# ADCs.net
KiCad netlist of a schematic drawn in Altium Designer
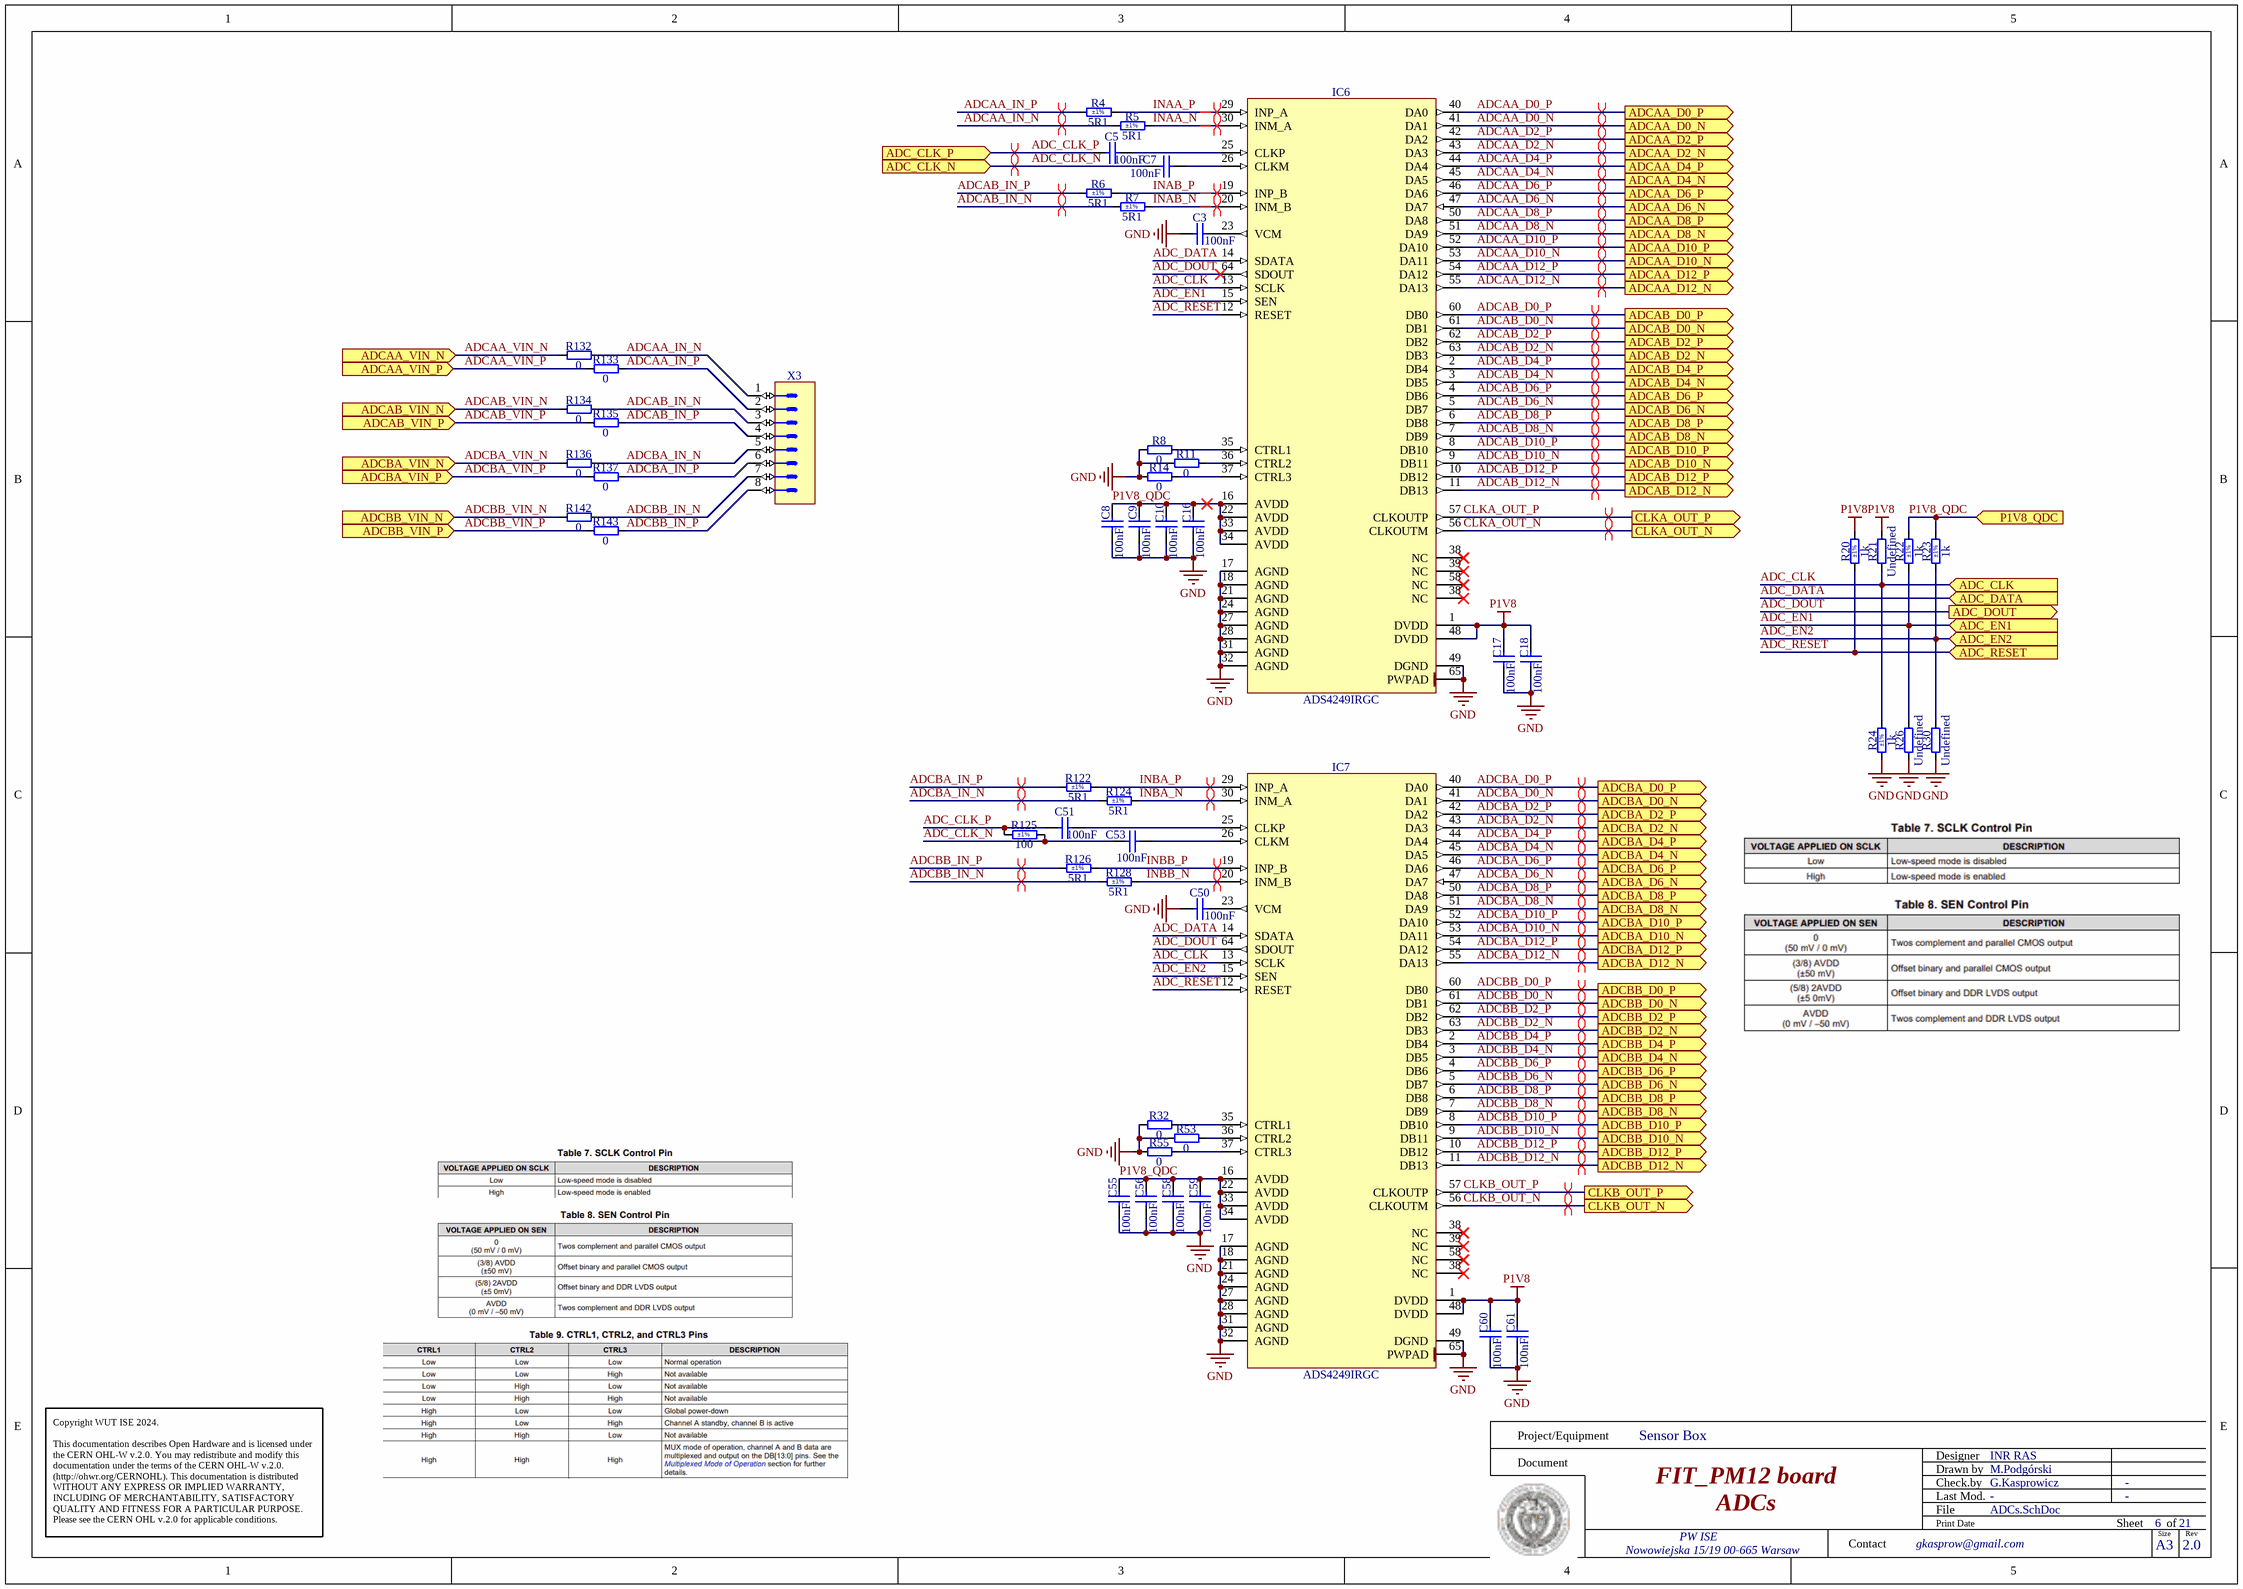
[diagram p0: ADCs.SchDoc]

(export (version "E")
  (design (tool "Eeschema 10.0.6"))
  (components
    (comp (ref "C3")
      (value "100nF")
      (footprint "CAPC1005X55N")
      (description "Non-polarised capacitor")
      (fields
        (field (name "PART NUMBER") "CC0402_100NF_16V_10%_X5R")
        (field (name "VOLTAGE") "16V")
        (field (name "AUTHOR") "CERN DEM JLC")
      )
      (libsource (lib "Capacitors") (part "Capacitor - non polarized"))
    )
    (comp (ref "C5")
      (value "100nF")
      (footprint "CAPC1005X55N")
      (description "Non-polarised capacitor")
      (fields
        (field (name "PART NUMBER") "CC0402_100NF_16V_10%_X5R")
        (field (name "VOLTAGE") "16V")
        (field (name "AUTHOR") "CERN DEM JLC")
      )
      (libsource (lib "Capacitors") (part "Capacitor - non polarized"))
    )
    (comp (ref "C7")
      (value "100nF")
      (footprint "CAPC1005X55N")
      (description "Non-polarised capacitor")
      (fields
        (field (name "PART NUMBER") "CC0402_100NF_16V_10%_X5R")
        (field (name "VOLTAGE") "16V")
        (field (name "AUTHOR") "CERN DEM JLC")
      )
      (libsource (lib "Capacitors") (part "Capacitor - non polarized"))
    )
    (comp (ref "C8")
      (value "100nF")
      (footprint "CAPC1005X55N")
      (description "Non-polarised capacitor")
      (fields
        (field (name "PART NUMBER") "CC0402_100NF_16V_10%_X5R")
        (field (name "VOLTAGE") "16V")
        (field (name "AUTHOR") "CERN DEM JLC")
      )
      (libsource (lib "Capacitors") (part "Capacitor - non polarized"))
    )
    (comp (ref "C9")
      (value "100nF")
      (footprint "CAPC1005X55N")
      (description "Non-polarised capacitor")
      (fields
        (field (name "PART NUMBER") "CC0402_100NF_16V_10%_X5R")
        (field (name "VOLTAGE") "16V")
        (field (name "AUTHOR") "CERN DEM JLC")
      )
      (libsource (lib "Capacitors") (part "Capacitor - non polarized"))
    )
    (comp (ref "C10")
      (value "100nF")
      (footprint "CAPC1005X55N")
      (description "Non-polarised capacitor")
      (fields
        (field (name "PART NUMBER") "CC0402_100NF_16V_10%_X5R")
        (field (name "VOLTAGE") "16V")
        (field (name "AUTHOR") "CERN DEM JLC")
      )
      (libsource (lib "Capacitors") (part "Capacitor - non polarized"))
    )
    (comp (ref "C16")
      (value "100nF")
      (footprint "CAPC1005X55N")
      (description "Non-polarised capacitor")
      (fields
        (field (name "PART NUMBER") "CC0402_100NF_16V_10%_X5R")
        (field (name "VOLTAGE") "16V")
        (field (name "AUTHOR") "CERN DEM JLC")
      )
      (libsource (lib "Capacitors") (part "Capacitor - non polarized"))
    )
    (comp (ref "C17")
      (value "100nF")
      (footprint "CAPC1005X55N")
      (description "Non-polarised capacitor")
      (fields
        (field (name "PART NUMBER") "CC0402_100NF_16V_10%_X5R")
        (field (name "VOLTAGE") "16V")
        (field (name "AUTHOR") "CERN DEM JLC")
      )
      (libsource (lib "Capacitors") (part "Capacitor - non polarized"))
    )
    (comp (ref "C18")
      (value "100nF")
      (footprint "CAPC1005X55N")
      (description "Non-polarised capacitor")
      (fields
        (field (name "PART NUMBER") "CC0402_100NF_16V_10%_X5R")
        (field (name "VOLTAGE") "16V")
        (field (name "AUTHOR") "CERN DEM JLC")
      )
      (libsource (lib "Capacitors") (part "Capacitor - non polarized"))
    )
    (comp (ref "C50")
      (value "100nF")
      (footprint "CAPC1005X55N")
      (description "Non-polarised capacitor")
      (fields
        (field (name "PART NUMBER") "CC0402_100NF_16V_10%_X5R")
        (field (name "VOLTAGE") "16V")
        (field (name "AUTHOR") "CERN DEM JLC")
      )
      (libsource (lib "Capacitors") (part "Capacitor - non polarized"))
    )
    (comp (ref "C51")
      (value "100nF")
      (footprint "CAPC1005X55N")
      (description "Non-polarised capacitor")
      (fields
        (field (name "PART NUMBER") "CC0402_100NF_16V_10%_X5R")
        (field (name "VOLTAGE") "16V")
        (field (name "AUTHOR") "CERN DEM JLC")
      )
      (libsource (lib "Capacitors") (part "Capacitor - non polarized"))
    )
    (comp (ref "C53")
      (value "100nF")
      (footprint "CAPC1005X55N")
      (description "Non-polarised capacitor")
      (fields
        (field (name "PART NUMBER") "CC0402_100NF_16V_10%_X5R")
        (field (name "VOLTAGE") "16V")
        (field (name "AUTHOR") "CERN DEM JLC")
      )
      (libsource (lib "Capacitors") (part "Capacitor - non polarized"))
    )
    (comp (ref "C55")
      (value "100nF")
      (footprint "CAPC1005X55N")
      (description "Non-polarised capacitor")
      (fields
        (field (name "PART NUMBER") "CC0402_100NF_16V_10%_X5R")
        (field (name "VOLTAGE") "16V")
        (field (name "AUTHOR") "CERN DEM JLC")
      )
      (libsource (lib "Capacitors") (part "Capacitor - non polarized"))
    )
    (comp (ref "C56")
      (value "100nF")
      (footprint "CAPC1005X55N")
      (description "Non-polarised capacitor")
      (fields
        (field (name "PART NUMBER") "CC0402_100NF_16V_10%_X5R")
        (field (name "VOLTAGE") "16V")
        (field (name "AUTHOR") "CERN DEM JLC")
      )
      (libsource (lib "Capacitors") (part "Capacitor - non polarized"))
    )
    (comp (ref "C58")
      (value "100nF")
      (footprint "CAPC1005X55N")
      (description "Non-polarised capacitor")
      (fields
        (field (name "PART NUMBER") "CC0402_100NF_16V_10%_X5R")
        (field (name "VOLTAGE") "16V")
        (field (name "AUTHOR") "CERN DEM JLC")
      )
      (libsource (lib "Capacitors") (part "Capacitor - non polarized"))
    )
    (comp (ref "C59")
      (value "100nF")
      (footprint "CAPC1005X55N")
      (description "Non-polarised capacitor")
      (fields
        (field (name "PART NUMBER") "CC0402_100NF_16V_10%_X5R")
        (field (name "VOLTAGE") "16V")
        (field (name "AUTHOR") "CERN DEM JLC")
      )
      (libsource (lib "Capacitors") (part "Capacitor - non polarized"))
    )
    (comp (ref "C60")
      (value "100nF")
      (footprint "CAPC1005X55N")
      (description "Non-polarised capacitor")
      (fields
        (field (name "PART NUMBER") "CC0402_100NF_16V_10%_X5R")
        (field (name "VOLTAGE") "16V")
        (field (name "AUTHOR") "CERN DEM JLC")
      )
      (libsource (lib "Capacitors") (part "Capacitor - non polarized"))
    )
    (comp (ref "C61")
      (value "100nF")
      (footprint "CAPC1005X55N")
      (description "Non-polarised capacitor")
      (fields
        (field (name "PART NUMBER") "CC0402_100NF_16V_10%_X5R")
        (field (name "VOLTAGE") "16V")
        (field (name "AUTHOR") "CERN DEM JLC")
      )
      (libsource (lib "Capacitors") (part "Capacitor - non polarized"))
    )
    (comp (ref "IC6")
      (value "ADS4249IRGC")
      (footprint "QFN50P900X900X100-65N-S750")
      (description "16-Bit, 200-MSPS Analog-to-Digital Converters")
      (fields (field (name "MANUFACTURER") "TEXAS INSTRUMENTS") (field (name "AUTHOR") "CERN DEM HF"))
      (libsource (lib "ICs And Semiconductors") (part "ADS4249IRGC"))
    )
    (comp (ref "IC7")
      (value "ADS4249IRGC")
      (footprint "QFN50P900X900X100-65N-S750")
      (description "16-Bit, 200-MSPS Analog-to-Digital Converters")
      (fields (field (name "MANUFACTURER") "TEXAS INSTRUMENTS") (field (name "AUTHOR") "CERN DEM HF"))
      (libsource (lib "ICs And Semiconductors") (part "ADS4249IRGC"))
    )
    (comp (ref "R4")
      (value "5R1")
      (footprint "RESC1005X40N")
      (description "Resistor - 1%")
      (fields
        (field (name "TOLERANCE") "±1%")
        (field (name "PART NUMBER") "R0402_5R1_1%_0.0625W_100PPM")
        (field (name "POWER") "0.0625W")
        (field (name "AUTHOR") "CERN DEM MR")
      )
      (libsource (lib "Resistors") (part "Resistor - 1%"))
    )
    (comp (ref "R5")
      (value "5R1")
      (footprint "RESC1005X40N")
      (description "Resistor - 1%")
      (fields
        (field (name "TOLERANCE") "±1%")
        (field (name "PART NUMBER") "R0402_5R1_1%_0.0625W_100PPM")
        (field (name "POWER") "0.0625W")
        (field (name "AUTHOR") "CERN DEM MR")
      )
      (libsource (lib "Resistors") (part "Resistor - 1%"))
    )
    (comp (ref "R6")
      (value "5R1")
      (footprint "RESC1005X40N")
      (description "Resistor - 1%")
      (fields
        (field (name "TOLERANCE") "±1%")
        (field (name "PART NUMBER") "R0402_5R1_1%_0.0625W_100PPM")
        (field (name "POWER") "0.0625W")
        (field (name "AUTHOR") "CERN DEM MR")
      )
      (libsource (lib "Resistors") (part "Resistor - 1%"))
    )
    (comp (ref "R7")
      (value "5R1")
      (footprint "RESC1005X40N")
      (description "Resistor - 1%")
      (fields
        (field (name "TOLERANCE") "±1%")
        (field (name "PART NUMBER") "R0402_5R1_1%_0.0625W_100PPM")
        (field (name "POWER") "0.0625W")
        (field (name "AUTHOR") "CERN DEM MR")
      )
      (libsource (lib "Resistors") (part "Resistor - 1%"))
    )
    (comp (ref "R8")
      (value "0")
      (footprint "RESC1005X40N")
      (description "Resistor")
      (fields
        (field (name "PART NUMBER") "R0402_0R_JUMPER")
        (field (name "MANUFACTURER") "GENERIC")
        (field (name "AUTHOR") "CERN DEM JLC")
      )
      (libsource (lib "Resistors") (part "Resistor"))
    )
    (comp (ref "R11")
      (value "0")
      (footprint "RESC1005X40N")
      (description "Resistor")
      (fields
        (field (name "PART NUMBER") "R0402_0R_JUMPER")
        (field (name "MANUFACTURER") "GENERIC")
        (field (name "AUTHOR") "CERN DEM JLC")
      )
      (libsource (lib "Resistors") (part "Resistor"))
    )
    (comp (ref "R14")
      (value "0")
      (footprint "RESC1005X40N")
      (description "Resistor")
      (fields
        (field (name "PART NUMBER") "R0402_0R_JUMPER")
        (field (name "MANUFACTURER") "GENERIC")
        (field (name "AUTHOR") "CERN DEM JLC")
      )
      (libsource (lib "Resistors") (part "Resistor"))
    )
    (comp (ref "R20")
      (value "1k")
      (footprint "RESC1005X40N")
      (description "Resistor - 1%")
      (fields
        (field (name "TOLERANCE") "±1%")
        (field (name "PART NUMBER") "R0402_1K_1%_0.0625W_100PPM")
        (field (name "POWER") "0.0625W")
        (field (name "AUTHOR") "CERN DEM JLC")
      )
      (libsource (lib "Resistors") (part "Resistor - 1%"))
    )
    (comp (ref "R21")
      (value "Undefined")
      (footprint "RESC1005X40N")
      (description "Resistor")
      (fields (field (name "PART NUMBER") "R0402_NO-VALUE") (field (name "AUTHOR") "CERN DEM JLC"))
      (libsource (lib "Resistors") (part "Resistor"))
    )
    (comp (ref "R22")
      (value "1k")
      (footprint "RESC1005X40N")
      (description "Resistor - 1%")
      (fields
        (field (name "TOLERANCE") "±1%")
        (field (name "PART NUMBER") "R0402_1K_1%_0.0625W_100PPM")
        (field (name "POWER") "0.0625W")
        (field (name "AUTHOR") "CERN DEM JLC")
      )
      (libsource (lib "Resistors") (part "Resistor - 1%"))
    )
    (comp (ref "R23")
      (value "1k")
      (footprint "RESC1005X40N")
      (description "Resistor - 1%")
      (fields
        (field (name "TOLERANCE") "±1%")
        (field (name "PART NUMBER") "R0402_1K_1%_0.0625W_100PPM")
        (field (name "POWER") "0.0625W")
        (field (name "AUTHOR") "CERN DEM JLC")
      )
      (libsource (lib "Resistors") (part "Resistor - 1%"))
    )
    (comp (ref "R24")
      (value "1k")
      (footprint "RESC1005X40N")
      (description "Resistor - 1%")
      (fields
        (field (name "TOLERANCE") "±1%")
        (field (name "PART NUMBER") "R0402_1K_1%_0.0625W_100PPM")
        (field (name "POWER") "0.0625W")
        (field (name "AUTHOR") "CERN DEM JLC")
      )
      (libsource (lib "Resistors") (part "Resistor - 1%"))
    )
    (comp (ref "R26")
      (value "Undefined")
      (footprint "RESC1005X40N")
      (description "Resistor")
      (fields (field (name "PART NUMBER") "R0402_NO-VALUE") (field (name "AUTHOR") "CERN DEM JLC"))
      (libsource (lib "Resistors") (part "Resistor"))
    )
    (comp (ref "R30")
      (value "Undefined")
      (footprint "RESC1005X40N")
      (description "Resistor")
      (fields (field (name "PART NUMBER") "R0402_NO-VALUE") (field (name "AUTHOR") "CERN DEM JLC"))
      (libsource (lib "Resistors") (part "Resistor"))
    )
    (comp (ref "R32")
      (value "0")
      (footprint "RESC1005X40N")
      (description "Resistor")
      (fields
        (field (name "PART NUMBER") "R0402_0R_JUMPER")
        (field (name "MANUFACTURER") "GENERIC")
        (field (name "AUTHOR") "CERN DEM JLC")
      )
      (libsource (lib "Resistors") (part "Resistor"))
    )
    (comp (ref "R53")
      (value "0")
      (footprint "RESC1005X40N")
      (description "Resistor")
      (fields
        (field (name "PART NUMBER") "R0402_0R_JUMPER")
        (field (name "MANUFACTURER") "GENERIC")
        (field (name "AUTHOR") "CERN DEM JLC")
      )
      (libsource (lib "Resistors") (part "Resistor"))
    )
    (comp (ref "R55")
      (value "0")
      (footprint "RESC1005X40N")
      (description "Resistor")
      (fields
        (field (name "PART NUMBER") "R0402_0R_JUMPER")
        (field (name "MANUFACTURER") "GENERIC")
        (field (name "AUTHOR") "CERN DEM JLC")
      )
      (libsource (lib "Resistors") (part "Resistor"))
    )
    (comp (ref "R122")
      (value "5R1")
      (footprint "RESC1005X40N")
      (description "Resistor - 1%")
      (fields
        (field (name "TOLERANCE") "±1%")
        (field (name "PART NUMBER") "R0402_5R1_1%_0.0625W_100PPM")
        (field (name "POWER") "0.0625W")
        (field (name "AUTHOR") "CERN DEM MR")
      )
      (libsource (lib "Resistors") (part "Resistor - 1%"))
    )
    (comp (ref "R124")
      (value "5R1")
      (footprint "RESC1005X40N")
      (description "Resistor - 1%")
      (fields
        (field (name "TOLERANCE") "±1%")
        (field (name "PART NUMBER") "R0402_5R1_1%_0.0625W_100PPM")
        (field (name "POWER") "0.0625W")
        (field (name "AUTHOR") "CERN DEM MR")
      )
      (libsource (lib "Resistors") (part "Resistor - 1%"))
    )
    (comp (ref "R125")
      (value "100")
      (footprint "RESC1608X55N")
      (description "Resistor - 1%")
      (fields
        (field (name "TOLERANCE") "±1%")
        (field (name "PART NUMBER") "R0603_100R_1%_0.1W_100PPM")
        (field (name "POWER") "0.1W")
        (field (name "AUTHOR") "CERN DEM JLC")
      )
      (libsource (lib "Resistors") (part "Resistor - 1%"))
    )
    (comp (ref "R126")
      (value "5R1")
      (footprint "RESC1005X40N")
      (description "Resistor - 1%")
      (fields
        (field (name "TOLERANCE") "±1%")
        (field (name "PART NUMBER") "R0402_5R1_1%_0.0625W_100PPM")
        (field (name "POWER") "0.0625W")
        (field (name "AUTHOR") "CERN DEM MR")
      )
      (libsource (lib "Resistors") (part "Resistor - 1%"))
    )
    (comp (ref "R128")
      (value "5R1")
      (footprint "RESC1005X40N")
      (description "Resistor - 1%")
      (fields
        (field (name "TOLERANCE") "±1%")
        (field (name "PART NUMBER") "R0402_5R1_1%_0.0625W_100PPM")
        (field (name "POWER") "0.0625W")
        (field (name "AUTHOR") "CERN DEM MR")
      )
      (libsource (lib "Resistors") (part "Resistor - 1%"))
    )
    (comp (ref "R132")
      (value "0")
      (footprint "RESC1005X40N")
      (description "Resistor")
      (fields
        (field (name "PART NUMBER") "R0402_0R_JUMPER")
        (field (name "MANUFACTURER") "GENERIC")
        (field (name "AUTHOR") "CERN DEM JLC")
      )
      (libsource (lib "Resistors") (part "Resistor"))
    )
    (comp (ref "R133")
      (value "0")
      (footprint "RESC1005X40N")
      (description "Resistor")
      (fields
        (field (name "PART NUMBER") "R0402_0R_JUMPER")
        (field (name "MANUFACTURER") "GENERIC")
        (field (name "AUTHOR") "CERN DEM JLC")
      )
      (libsource (lib "Resistors") (part "Resistor"))
    )
    (comp (ref "R134")
      (value "0")
      (footprint "RESC1005X40N")
      (description "Resistor")
      (fields
        (field (name "PART NUMBER") "R0402_0R_JUMPER")
        (field (name "MANUFACTURER") "GENERIC")
        (field (name "AUTHOR") "CERN DEM JLC")
      )
      (libsource (lib "Resistors") (part "Resistor"))
    )
    (comp (ref "R135")
      (value "0")
      (footprint "RESC1005X40N")
      (description "Resistor")
      (fields
        (field (name "PART NUMBER") "R0402_0R_JUMPER")
        (field (name "MANUFACTURER") "GENERIC")
        (field (name "AUTHOR") "CERN DEM JLC")
      )
      (libsource (lib "Resistors") (part "Resistor"))
    )
    (comp (ref "R136")
      (value "0")
      (footprint "RESC1005X40N")
      (description "Resistor")
      (fields
        (field (name "PART NUMBER") "R0402_0R_JUMPER")
        (field (name "MANUFACTURER") "GENERIC")
        (field (name "AUTHOR") "CERN DEM JLC")
      )
      (libsource (lib "Resistors") (part "Resistor"))
    )
    (comp (ref "R137")
      (value "0")
      (footprint "RESC1005X40N")
      (description "Resistor")
      (fields
        (field (name "PART NUMBER") "R0402_0R_JUMPER")
        (field (name "MANUFACTURER") "GENERIC")
        (field (name "AUTHOR") "CERN DEM JLC")
      )
      (libsource (lib "Resistors") (part "Resistor"))
    )
    (comp (ref "R142")
      (value "0")
      (footprint "RESC1005X40N")
      (description "Resistor")
      (fields
        (field (name "PART NUMBER") "R0402_0R_JUMPER")
        (field (name "MANUFACTURER") "GENERIC")
        (field (name "AUTHOR") "CERN DEM JLC")
      )
      (libsource (lib "Resistors") (part "Resistor"))
    )
    (comp (ref "R143")
      (value "0")
      (footprint "RESC1005X40N")
      (description "Resistor")
      (fields
        (field (name "PART NUMBER") "R0402_0R_JUMPER")
        (field (name "MANUFACTURER") "GENERIC")
        (field (name "AUTHOR") "CERN DEM JLC")
      )
      (libsource (lib "Resistors") (part "Resistor"))
    )
    (comp (ref "X3")
      (value "Header 8")
      (footprint "SAMTEC_DW-08-09-L-S-470")
      (description "Connector 8 Male")
      (fields
        (field (name "PART NUMBER") "SAMTEC_DW-08-09-L-S-470")
        (field (name "MANUFACTURER") "SAMTEC")
        (field (name "AUTHOR") "CERN DEM HF")
      )
      (libsource (lib "Connectors") (part "Connector 8 Male"))
    )
  )
  (nets
    (net (code "1") (name "/ADCAA_D0_N") (class "Default")
      (node (ref "IC6") (pin "41") (pinfunction "DA1_41") (pintype "output"))
    )
    (net (code "2") (name "/ADCAA_D0_P") (class "Default")
      (node (ref "IC6") (pin "40") (pinfunction "DA0_40") (pintype "output"))
    )
    (net (code "3") (name "/ADCAA_D2_N") (class "Default")
      (node (ref "IC6") (pin "43") (pinfunction "DA3_43") (pintype "output"))
    )
    (net (code "4") (name "/ADCAA_D2_P") (class "Default")
      (node (ref "IC6") (pin "42") (pinfunction "DA2_42") (pintype "output"))
    )
    (net (code "5") (name "/ADCAA_D4_N") (class "Default")
      (node (ref "IC6") (pin "45") (pinfunction "DA5_45") (pintype "output"))
    )
    (net (code "6") (name "/ADCAA_D4_P") (class "Default")
      (node (ref "IC6") (pin "44") (pinfunction "DA4_44") (pintype "output"))
    )
    (net (code "7") (name "/ADCAA_D6_N") (class "Default")
      (node (ref "IC6") (pin "47") (pinfunction "DA7_47") (pintype "input"))
    )
    (net (code "8") (name "/ADCAA_D6_P") (class "Default")
      (node (ref "IC6") (pin "46") (pinfunction "DA6_46") (pintype "output"))
    )
    (net (code "9") (name "/ADCAA_D8_N") (class "Default")
      (node (ref "IC6") (pin "51") (pinfunction "DA9_51") (pintype "output"))
    )
    (net (code "10") (name "/ADCAA_D8_P") (class "Default")
      (node (ref "IC6") (pin "50") (pinfunction "DA8_50") (pintype "output"))
    )
    (net (code "11") (name "/ADCAA_D10_N") (class "Default")
      (node (ref "IC6") (pin "53") (pinfunction "DA11_53") (pintype "output"))
    )
    (net (code "12") (name "/ADCAA_D10_P") (class "Default")
      (node (ref "IC6") (pin "52") (pinfunction "DA10_52") (pintype "output"))
    )
    (net (code "13") (name "/ADCAA_D12_N") (class "Default")
      (node (ref "IC6") (pin "55") (pinfunction "DA13_55") (pintype "output"))
    )
    (net (code "14") (name "/ADCAA_D12_P") (class "Default")
      (node (ref "IC6") (pin "54") (pinfunction "DA12_54") (pintype "output"))
    )
    (net (code "15") (name "/ADCAA_IN_N") (class "Default")
      (node (ref "R132") (pin "2") (pinfunction "2_2") (pintype "passive"))
      (node (ref "R5") (pin "1") (pinfunction "1_1") (pintype "passive"))
      (node (ref "X3") (pin "1") (pinfunction "1_1") (pintype "bidirectional"))
    )
    (net (code "16") (name "/ADCAA_IN_P") (class "Default")
      (node (ref "R133") (pin "2") (pinfunction "2_2") (pintype "passive"))
      (node (ref "R4") (pin "1") (pinfunction "1_1") (pintype "passive"))
      (node (ref "X3") (pin "2") (pinfunction "2_2") (pintype "bidirectional"))
    )
    (net (code "17") (name "/ADCAA_VIN_N") (class "Default")
      (node (ref "R132") (pin "1") (pinfunction "1_1") (pintype "passive"))
    )
    (net (code "18") (name "/ADCAA_VIN_P") (class "Default")
      (node (ref "R133") (pin "1") (pinfunction "1_1") (pintype "passive"))
    )
    (net (code "19") (name "/ADCAB_D0_N") (class "Default")
      (node (ref "IC6") (pin "61") (pinfunction "DB1_61") (pintype "output"))
    )
    (net (code "20") (name "/ADCAB_D0_P") (class "Default")
      (node (ref "IC6") (pin "60") (pinfunction "DB0_60") (pintype "output"))
    )
    (net (code "21") (name "/ADCAB_D2_N") (class "Default")
      (node (ref "IC6") (pin "63") (pinfunction "DB3_63") (pintype "output"))
    )
    (net (code "22") (name "/ADCAB_D2_P") (class "Default")
      (node (ref "IC6") (pin "62") (pinfunction "DB2_62") (pintype "output"))
    )
    (net (code "23") (name "/ADCAB_D4_N") (class "Default")
      (node (ref "IC6") (pin "3") (pinfunction "DB5_3") (pintype "output"))
    )
    (net (code "24") (name "/ADCAB_D4_P") (class "Default")
      (node (ref "IC6") (pin "2") (pinfunction "DB4_2") (pintype "output"))
    )
    (net (code "25") (name "/ADCAB_D6_N") (class "Default")
      (node (ref "IC6") (pin "5") (pinfunction "DB7_5") (pintype "output"))
    )
    (net (code "26") (name "/ADCAB_D6_P") (class "Default")
      (node (ref "IC6") (pin "4") (pinfunction "DB6_4") (pintype "output"))
    )
    (net (code "27") (name "/ADCAB_D8_N") (class "Default")
      (node (ref "IC6") (pin "7") (pinfunction "DB9_7") (pintype "output"))
    )
    (net (code "28") (name "/ADCAB_D8_P") (class "Default")
      (node (ref "IC6") (pin "6") (pinfunction "DB8_6") (pintype "output"))
    )
    (net (code "29") (name "/ADCAB_D10_N") (class "Default")
      (node (ref "IC6") (pin "9") (pinfunction "DB11_9") (pintype "output"))
    )
    (net (code "30") (name "/ADCAB_D10_P") (class "Default")
      (node (ref "IC6") (pin "8") (pinfunction "DB10_8") (pintype "output"))
    )
    (net (code "31") (name "/ADCAB_D12_N") (class "Default")
      (node (ref "IC6") (pin "11") (pinfunction "DB13_11") (pintype "output"))
    )
    (net (code "32") (name "/ADCAB_D12_P") (class "Default")
      (node (ref "IC6") (pin "10") (pinfunction "DB12_10") (pintype "output"))
    )
    (net (code "33") (name "/ADCAB_IN_N") (class "Default")
      (node (ref "R134") (pin "2") (pinfunction "2_2") (pintype "passive"))
      (node (ref "R7") (pin "1") (pinfunction "1_1") (pintype "passive"))
      (node (ref "X3") (pin "3") (pinfunction "3_3") (pintype "bidirectional"))
    )
    (net (code "34") (name "/ADCAB_IN_P") (class "Default")
      (node (ref "R135") (pin "2") (pinfunction "2_2") (pintype "passive"))
      (node (ref "R6") (pin "1") (pinfunction "1_1") (pintype "passive"))
      (node (ref "X3") (pin "4") (pinfunction "4_4") (pintype "bidirectional"))
    )
    (net (code "35") (name "/ADCAB_VIN_N") (class "Default")
      (node (ref "R134") (pin "1") (pinfunction "1_1") (pintype "passive"))
    )
    (net (code "36") (name "/ADCAB_VIN_P") (class "Default")
      (node (ref "R135") (pin "1") (pinfunction "1_1") (pintype "passive"))
    )
    (net (code "37") (name "/ADCBA_D0_N") (class "Default")
      (node (ref "IC7") (pin "41") (pinfunction "DA1_41") (pintype "output"))
    )
    (net (code "38") (name "/ADCBA_D0_P") (class "Default")
      (node (ref "IC7") (pin "40") (pinfunction "DA0_40") (pintype "output"))
    )
    (net (code "39") (name "/ADCBA_D2_N") (class "Default")
      (node (ref "IC7") (pin "43") (pinfunction "DA3_43") (pintype "output"))
    )
    (net (code "40") (name "/ADCBA_D2_P") (class "Default")
      (node (ref "IC7") (pin "42") (pinfunction "DA2_42") (pintype "output"))
    )
    (net (code "41") (name "/ADCBA_D4_N") (class "Default")
      (node (ref "IC7") (pin "45") (pinfunction "DA5_45") (pintype "output"))
    )
    (net (code "42") (name "/ADCBA_D4_P") (class "Default")
      (node (ref "IC7") (pin "44") (pinfunction "DA4_44") (pintype "output"))
    )
    (net (code "43") (name "/ADCBA_D6_N") (class "Default")
      (node (ref "IC7") (pin "47") (pinfunction "DA7_47") (pintype "input"))
    )
    (net (code "44") (name "/ADCBA_D6_P") (class "Default")
      (node (ref "IC7") (pin "46") (pinfunction "DA6_46") (pintype "output"))
    )
    (net (code "45") (name "/ADCBA_D8_N") (class "Default")
      (node (ref "IC7") (pin "51") (pinfunction "DA9_51") (pintype "output"))
    )
    (net (code "46") (name "/ADCBA_D8_P") (class "Default")
      (node (ref "IC7") (pin "50") (pinfunction "DA8_50") (pintype "output"))
    )
    (net (code "47") (name "/ADCBA_D10_N") (class "Default")
      (node (ref "IC7") (pin "53") (pinfunction "DA11_53") (pintype "output"))
    )
    (net (code "48") (name "/ADCBA_D10_P") (class "Default")
      (node (ref "IC7") (pin "52") (pinfunction "DA10_52") (pintype "output"))
    )
    (net (code "49") (name "/ADCBA_D12_N") (class "Default")
      (node (ref "IC7") (pin "55") (pinfunction "DA13_55") (pintype "output"))
    )
    (net (code "50") (name "/ADCBA_D12_P") (class "Default")
      (node (ref "IC7") (pin "54") (pinfunction "DA12_54") (pintype "output"))
    )
    (net (code "51") (name "/ADCBA_IN_N") (class "Default")
      (node (ref "R124") (pin "1") (pinfunction "1_1") (pintype "passive"))
      (node (ref "R136") (pin "2") (pinfunction "2_2") (pintype "passive"))
      (node (ref "X3") (pin "5") (pinfunction "5_5") (pintype "bidirectional"))
    )
    (net (code "52") (name "/ADCBA_IN_P") (class "Default")
      (node (ref "R122") (pin "1") (pinfunction "1_1") (pintype "passive"))
      (node (ref "R137") (pin "2") (pinfunction "2_2") (pintype "passive"))
      (node (ref "X3") (pin "6") (pinfunction "6_6") (pintype "bidirectional"))
    )
    (net (code "53") (name "/ADCBA_VIN_N") (class "Default")
      (node (ref "R136") (pin "1") (pinfunction "1_1") (pintype "passive"))
    )
    (net (code "54") (name "/ADCBA_VIN_P") (class "Default")
      (node (ref "R137") (pin "1") (pinfunction "1_1") (pintype "passive"))
    )
    (net (code "55") (name "/ADCBB_D0_N") (class "Default")
      (node (ref "IC7") (pin "61") (pinfunction "DB1_61") (pintype "output"))
    )
    (net (code "56") (name "/ADCBB_D0_P") (class "Default")
      (node (ref "IC7") (pin "60") (pinfunction "DB0_60") (pintype "output"))
    )
    (net (code "57") (name "/ADCBB_D2_N") (class "Default")
      (node (ref "IC7") (pin "63") (pinfunction "DB3_63") (pintype "output"))
    )
    (net (code "58") (name "/ADCBB_D2_P") (class "Default")
      (node (ref "IC7") (pin "62") (pinfunction "DB2_62") (pintype "output"))
    )
    (net (code "59") (name "/ADCBB_D4_N") (class "Default")
      (node (ref "IC7") (pin "3") (pinfunction "DB5_3") (pintype "output"))
    )
    (net (code "60") (name "/ADCBB_D4_P") (class "Default")
      (node (ref "IC7") (pin "2") (pinfunction "DB4_2") (pintype "output"))
    )
    (net (code "61") (name "/ADCBB_D6_N") (class "Default")
      (node (ref "IC7") (pin "5") (pinfunction "DB7_5") (pintype "output"))
    )
    (net (code "62") (name "/ADCBB_D6_P") (class "Default")
      (node (ref "IC7") (pin "4") (pinfunction "DB6_4") (pintype "output"))
    )
    (net (code "63") (name "/ADCBB_D8_N") (class "Default")
      (node (ref "IC7") (pin "7") (pinfunction "DB9_7") (pintype "output"))
    )
    (net (code "64") (name "/ADCBB_D8_P") (class "Default")
      (node (ref "IC7") (pin "6") (pinfunction "DB8_6") (pintype "output"))
    )
    (net (code "65") (name "/ADCBB_D10_N") (class "Default")
      (node (ref "IC7") (pin "9") (pinfunction "DB11_9") (pintype "output"))
    )
    (net (code "66") (name "/ADCBB_D10_P") (class "Default")
      (node (ref "IC7") (pin "8") (pinfunction "DB10_8") (pintype "output"))
    )
    (net (code "67") (name "/ADCBB_D12_N") (class "Default")
      (node (ref "IC7") (pin "11") (pinfunction "DB13_11") (pintype "output"))
    )
    (net (code "68") (name "/ADCBB_D12_P") (class "Default")
      (node (ref "IC7") (pin "10") (pinfunction "DB12_10") (pintype "output"))
    )
    (net (code "69") (name "/ADCBB_IN_N") (class "Default")
      (node (ref "R128") (pin "1") (pinfunction "1_1") (pintype "passive"))
      (node (ref "R142") (pin "2") (pinfunction "2_2") (pintype "passive"))
      (node (ref "X3") (pin "7") (pinfunction "7_7") (pintype "bidirectional"))
    )
    (net (code "70") (name "/ADCBB_IN_P") (class "Default")
      (node (ref "R126") (pin "1") (pinfunction "1_1") (pintype "passive"))
      (node (ref "R143") (pin "2") (pinfunction "2_2") (pintype "passive"))
      (node (ref "X3") (pin "8") (pinfunction "8_8") (pintype "bidirectional"))
    )
    (net (code "71") (name "/ADCBB_VIN_N") (class "Default")
      (node (ref "R142") (pin "1") (pinfunction "1_1") (pintype "passive"))
    )
    (net (code "72") (name "/ADCBB_VIN_P") (class "Default")
      (node (ref "R143") (pin "1") (pinfunction "1_1") (pintype "passive"))
    )
    (net (code "73") (name "/ADC_CLK") (class "Default")
      (node (ref "IC6") (pin "13") (pinfunction "SCLK_13") (pintype "input"))
      (node (ref "IC7") (pin "13") (pinfunction "SCLK_13") (pintype "input"))
      (node (ref "R21") (pin "1") (pinfunction "1_1") (pintype "passive"))
      (node (ref "R24") (pin "2") (pinfunction "2_2") (pintype "passive"))
    )
    (net (code "74") (name "/ADC_CLK_N") (class "Default")
      (node (ref "C53") (pin "1") (pinfunction "1_1") (pintype "passive"))
      (node (ref "C7") (pin "1") (pinfunction "1_1") (pintype "passive"))
      (node (ref "R125") (pin "2") (pinfunction "2_2") (pintype "passive"))
    )
    (net (code "75") (name "/ADC_CLK_P") (class "Default")
      (node (ref "C5") (pin "1") (pinfunction "1_1") (pintype "passive"))
      (node (ref "C51") (pin "1") (pinfunction "1_1") (pintype "passive"))
      (node (ref "R125") (pin "1") (pinfunction "1_1") (pintype "passive"))
    )
    (net (code "76") (name "/ADC_DATA") (class "Default")
      (node (ref "IC6") (pin "14") (pinfunction "SDATA_14") (pintype "input"))
      (node (ref "IC7") (pin "14") (pinfunction "SDATA_14") (pintype "input"))
    )
    (net (code "77") (name "/ADC_DOUT") (class "Default")
      (node (ref "IC6") (pin "64") (pinfunction "SDOUT_64") (pintype "output"))
      (node (ref "IC7") (pin "64") (pinfunction "SDOUT_64") (pintype "output"))
    )
    (net (code "78") (name "/ADC_EN1") (class "Default")
      (node (ref "IC6") (pin "15") (pinfunction "SEN_15") (pintype "input"))
      (node (ref "R22") (pin "1") (pinfunction "1_1") (pintype "passive"))
      (node (ref "R26") (pin "2") (pinfunction "2_2") (pintype "passive"))
    )
    (net (code "79") (name "/ADC_EN2") (class "Default")
      (node (ref "IC7") (pin "15") (pinfunction "SEN_15") (pintype "input"))
      (node (ref "R23") (pin "1") (pinfunction "1_1") (pintype "passive"))
      (node (ref "R30") (pin "2") (pinfunction "2_2") (pintype "passive"))
    )
    (net (code "80") (name "/ADC_RESET") (class "Default")
      (node (ref "IC6") (pin "12") (pinfunction "RESET_12") (pintype "input"))
      (node (ref "IC7") (pin "12") (pinfunction "RESET_12") (pintype "input"))
      (node (ref "R20") (pin "1") (pinfunction "1_1") (pintype "passive"))
    )
    (net (code "81") (name "/CLKA_OUT_N") (class "Default")
      (node (ref "IC6") (pin "56") (pinfunction "CLKOUTM_56") (pintype "output"))
    )
    (net (code "82") (name "/CLKA_OUT_P") (class "Default")
      (node (ref "IC6") (pin "57") (pinfunction "CLKOUTP_57") (pintype "output"))
    )
    (net (code "83") (name "/CLKB_OUT_N") (class "Default")
      (node (ref "IC7") (pin "56") (pinfunction "CLKOUTM_56") (pintype "output"))
    )
    (net (code "84") (name "/CLKB_OUT_P") (class "Default")
      (node (ref "IC7") (pin "57") (pinfunction "CLKOUTP_57") (pintype "output"))
    )
    (net (code "85") (name "/INAA_N") (class "Default")
      (node (ref "IC6") (pin "30") (pinfunction "INM_A_30") (pintype "input"))
      (node (ref "R5") (pin "2") (pinfunction "2_2") (pintype "passive"))
    )
    (net (code "86") (name "/INAA_P") (class "Default")
      (node (ref "IC6") (pin "29") (pinfunction "INP_A_29") (pintype "input"))
      (node (ref "R4") (pin "2") (pinfunction "2_2") (pintype "passive"))
    )
    (net (code "87") (name "/INAB_N") (class "Default")
      (node (ref "IC6") (pin "20") (pinfunction "INM_B_20") (pintype "input"))
      (node (ref "R7") (pin "2") (pinfunction "2_2") (pintype "passive"))
    )
    (net (code "88") (name "/INAB_P") (class "Default")
      (node (ref "IC6") (pin "19") (pinfunction "INP_B_19") (pintype "input"))
      (node (ref "R6") (pin "2") (pinfunction "2_2") (pintype "passive"))
    )
    (net (code "89") (name "/INBA_N") (class "Default")
      (node (ref "IC7") (pin "30") (pinfunction "INM_A_30") (pintype "input"))
      (node (ref "R124") (pin "2") (pinfunction "2_2") (pintype "passive"))
    )
    (net (code "90") (name "/INBA_P") (class "Default")
      (node (ref "IC7") (pin "29") (pinfunction "INP_A_29") (pintype "input"))
      (node (ref "R122") (pin "2") (pinfunction "2_2") (pintype "passive"))
    )
    (net (code "91") (name "/INBB_N") (class "Default")
      (node (ref "IC7") (pin "20") (pinfunction "INM_B_20") (pintype "input"))
      (node (ref "R128") (pin "2") (pinfunction "2_2") (pintype "passive"))
    )
    (net (code "92") (name "/INBB_P") (class "Default")
      (node (ref "IC7") (pin "19") (pinfunction "INP_B_19") (pintype "input"))
      (node (ref "R126") (pin "2") (pinfunction "2_2") (pintype "passive"))
    )
    (net (code "93") (name "/P1V8_QDC") (class "Default")
      (node (ref "C10") (pin "2") (pinfunction "2_2") (pintype "passive"))
      (node (ref "C16") (pin "2") (pinfunction "2_2") (pintype "passive"))
      (node (ref "C55") (pin "2") (pinfunction "2_2") (pintype "passive"))
      (node (ref "C56") (pin "2") (pinfunction "2_2") (pintype "passive"))
      (node (ref "C58") (pin "2") (pinfunction "2_2") (pintype "passive"))
      (node (ref "C59") (pin "2") (pinfunction "2_2") (pintype "passive"))
      (node (ref "C8") (pin "2") (pinfunction "2_2") (pintype "passive"))
      (node (ref "C9") (pin "2") (pinfunction "2_2") (pintype "passive"))
      (node (ref "IC6") (pin "16") (pinfunction "AVDD_16") (pintype "power_in"))
      (node (ref "IC6") (pin "22") (pinfunction "AVDD_22") (pintype "power_in"))
      (node (ref "IC6") (pin "33") (pinfunction "AVDD_33") (pintype "power_in"))
      (node (ref "IC6") (pin "34") (pinfunction "AVDD_34") (pintype "power_in"))
      (node (ref "IC7") (pin "16") (pinfunction "AVDD_16") (pintype "power_in"))
      (node (ref "IC7") (pin "22") (pinfunction "AVDD_22") (pintype "power_in"))
      (node (ref "IC7") (pin "33") (pinfunction "AVDD_33") (pintype "power_in"))
      (node (ref "IC7") (pin "34") (pinfunction "AVDD_34") (pintype "power_in"))
      (node (ref "R22") (pin "2") (pinfunction "2_2") (pintype "passive"))
      (node (ref "R23") (pin "2") (pinfunction "2_2") (pintype "passive"))
    )
    (net (code "94") (name "GND") (class "Default")
      (node (ref "C10") (pin "1") (pinfunction "1_1") (pintype "passive"))
      (node (ref "C16") (pin "1") (pinfunction "1_1") (pintype "passive"))
      (node (ref "C17") (pin "1") (pinfunction "1_1") (pintype "passive"))
      (node (ref "C18") (pin "1") (pinfunction "1_1") (pintype "passive"))
      (node (ref "C3") (pin "1") (pinfunction "1_1") (pintype "passive"))
      (node (ref "C50") (pin "1") (pinfunction "1_1") (pintype "passive"))
      (node (ref "C55") (pin "1") (pinfunction "1_1") (pintype "passive"))
      (node (ref "C56") (pin "1") (pinfunction "1_1") (pintype "passive"))
      (node (ref "C58") (pin "1") (pinfunction "1_1") (pintype "passive"))
      (node (ref "C59") (pin "1") (pinfunction "1_1") (pintype "passive"))
      (node (ref "C60") (pin "1") (pinfunction "1_1") (pintype "passive"))
      (node (ref "C61") (pin "1") (pinfunction "1_1") (pintype "passive"))
      (node (ref "C8") (pin "1") (pinfunction "1_1") (pintype "passive"))
      (node (ref "C9") (pin "1") (pinfunction "1_1") (pintype "passive"))
      (node (ref "IC6") (pin "17") (pinfunction "AGND_17") (pintype "power_in"))
      (node (ref "IC6") (pin "18") (pinfunction "AGND_18") (pintype "power_in"))
      (node (ref "IC6") (pin "21") (pinfunction "AGND_21") (pintype "power_in"))
      (node (ref "IC6") (pin "24") (pinfunction "AGND_24") (pintype "power_in"))
      (node (ref "IC6") (pin "27") (pinfunction "AGND_27") (pintype "power_in"))
      (node (ref "IC6") (pin "28") (pinfunction "AGND_28") (pintype "power_in"))
      (node (ref "IC6") (pin "31") (pinfunction "AGND_31") (pintype "power_in"))
      (node (ref "IC6") (pin "32") (pinfunction "AGND_32") (pintype "power_in"))
      (node (ref "IC6") (pin "49") (pinfunction "DGND_49") (pintype "power_in"))
      (node (ref "IC6") (pin "65") (pinfunction "PWPAD_65") (pintype "power_in"))
      (node (ref "IC7") (pin "17") (pinfunction "AGND_17") (pintype "power_in"))
      (node (ref "IC7") (pin "18") (pinfunction "AGND_18") (pintype "power_in"))
      (node (ref "IC7") (pin "21") (pinfunction "AGND_21") (pintype "power_in"))
      (node (ref "IC7") (pin "24") (pinfunction "AGND_24") (pintype "power_in"))
      (node (ref "IC7") (pin "27") (pinfunction "AGND_27") (pintype "power_in"))
      (node (ref "IC7") (pin "28") (pinfunction "AGND_28") (pintype "power_in"))
      (node (ref "IC7") (pin "31") (pinfunction "AGND_31") (pintype "power_in"))
      (node (ref "IC7") (pin "32") (pinfunction "AGND_32") (pintype "power_in"))
      (node (ref "IC7") (pin "49") (pinfunction "DGND_49") (pintype "power_in"))
      (node (ref "IC7") (pin "65") (pinfunction "PWPAD_65") (pintype "power_in"))
      (node (ref "R11") (pin "1") (pinfunction "1_1") (pintype "passive"))
      (node (ref "R14") (pin "1") (pinfunction "1_1") (pintype "passive"))
      (node (ref "R24") (pin "1") (pinfunction "1_1") (pintype "passive"))
      (node (ref "R26") (pin "1") (pinfunction "1_1") (pintype "passive"))
      (node (ref "R30") (pin "1") (pinfunction "1_1") (pintype "passive"))
      (node (ref "R32") (pin "1") (pinfunction "1_1") (pintype "passive"))
      (node (ref "R53") (pin "1") (pinfunction "1_1") (pintype "passive"))
      (node (ref "R55") (pin "1") (pinfunction "1_1") (pintype "passive"))
      (node (ref "R8") (pin "1") (pinfunction "1_1") (pintype "passive"))
    )
    (net (code "95") (name "Net-(IC6-CLKM)") (class "Default")
      (node (ref "C7") (pin "2") (pinfunction "2_2") (pintype "passive"))
      (node (ref "IC6") (pin "26") (pinfunction "CLKM_26") (pintype "input"))
    )
    (net (code "96") (name "Net-(IC6-CLKP)") (class "Default")
      (node (ref "C5") (pin "2") (pinfunction "2_2") (pintype "passive"))
      (node (ref "IC6") (pin "25") (pinfunction "CLKP_25") (pintype "input"))
    )
    (net (code "97") (name "Net-(IC6-CTRL1)") (class "Default")
      (node (ref "IC6") (pin "35") (pinfunction "CTRL1_35") (pintype "input"))
      (node (ref "R8") (pin "2") (pinfunction "2_2") (pintype "passive"))
    )
    (net (code "98") (name "Net-(IC6-CTRL2)") (class "Default")
      (node (ref "IC6") (pin "36") (pinfunction "CTRL2_36") (pintype "input"))
      (node (ref "R11") (pin "2") (pinfunction "2_2") (pintype "passive"))
    )
    (net (code "99") (name "Net-(IC6-CTRL3)") (class "Default")
      (node (ref "IC6") (pin "37") (pinfunction "CTRL3_37") (pintype "input"))
      (node (ref "R14") (pin "2") (pinfunction "2_2") (pintype "passive"))
    )
    (net (code "100") (name "Net-(IC6-VCM)") (class "Default")
      (node (ref "C3") (pin "2") (pinfunction "2_2") (pintype "passive"))
      (node (ref "IC6") (pin "23") (pinfunction "VCM_23") (pintype "output"))
    )
    (net (code "101") (name "Net-(IC7-CLKM)") (class "Default")
      (node (ref "C53") (pin "2") (pinfunction "2_2") (pintype "passive"))
      (node (ref "IC7") (pin "26") (pinfunction "CLKM_26") (pintype "input"))
    )
    (net (code "102") (name "Net-(IC7-CLKP)") (class "Default")
      (node (ref "C51") (pin "2") (pinfunction "2_2") (pintype "passive"))
      (node (ref "IC7") (pin "25") (pinfunction "CLKP_25") (pintype "input"))
    )
    (net (code "103") (name "Net-(IC7-CTRL1)") (class "Default")
      (node (ref "IC7") (pin "35") (pinfunction "CTRL1_35") (pintype "input"))
      (node (ref "R32") (pin "2") (pinfunction "2_2") (pintype "passive"))
    )
    (net (code "104") (name "Net-(IC7-CTRL2)") (class "Default")
      (node (ref "IC7") (pin "36") (pinfunction "CTRL2_36") (pintype "input"))
      (node (ref "R53") (pin "2") (pinfunction "2_2") (pintype "passive"))
    )
    (net (code "105") (name "Net-(IC7-CTRL3)") (class "Default")
      (node (ref "IC7") (pin "37") (pinfunction "CTRL3_37") (pintype "input"))
      (node (ref "R55") (pin "2") (pinfunction "2_2") (pintype "passive"))
    )
    (net (code "106") (name "Net-(IC7-VCM)") (class "Default")
      (node (ref "C50") (pin "2") (pinfunction "2_2") (pintype "passive"))
      (node (ref "IC7") (pin "23") (pinfunction "VCM_23") (pintype "output"))
    )
    (net (code "107") (name "P1V8") (class "Default")
      (node (ref "C17") (pin "2") (pinfunction "2_2") (pintype "passive"))
      (node (ref "C18") (pin "2") (pinfunction "2_2") (pintype "passive"))
      (node (ref "C60") (pin "2") (pinfunction "2_2") (pintype "passive"))
      (node (ref "C61") (pin "2") (pinfunction "2_2") (pintype "passive"))
      (node (ref "IC6") (pin "1") (pinfunction "DVDD_1") (pintype "power_in"))
      (node (ref "IC6") (pin "48") (pinfunction "DVDD_48") (pintype "power_in"))
      (node (ref "IC7") (pin "1") (pinfunction "DVDD_1") (pintype "power_in"))
      (node (ref "IC7") (pin "48") (pinfunction "DVDD_48") (pintype "power_in"))
      (node (ref "R20") (pin "2") (pinfunction "2_2") (pintype "passive"))
      (node (ref "R21") (pin "2") (pinfunction "2_2") (pintype "passive"))
    )
    (net (code "108") (name "unconnected-(IC6-NC-Pad38)") (class "Default")
      (node (ref "IC6") (pin "38") (pinfunction "NC_38") (pintype "passive+no_connect"))
    )
    (net (code "109") (name "unconnected-(IC6-NC-Pad38)_1") (class "Default")
      (node (ref "IC6") (pin "38") (pinfunction "NC_38") (pintype "passive+no_connect"))
    )
    (net (code "110") (name "unconnected-(IC6-NC-Pad39)") (class "Default")
      (node (ref "IC6") (pin "39") (pinfunction "NC_39") (pintype "passive+no_connect"))
    )
    (net (code "111") (name "unconnected-(IC6-NC-Pad58)") (class "Default")
      (node (ref "IC6") (pin "58") (pinfunction "NC_58") (pintype "passive+no_connect"))
    )
    (net (code "112") (name "unconnected-(IC7-NC-Pad38)") (class "Default")
      (node (ref "IC7") (pin "38") (pinfunction "NC_38") (pintype "passive+no_connect"))
    )
    (net (code "113") (name "unconnected-(IC7-NC-Pad38)_1") (class "Default")
      (node (ref "IC7") (pin "38") (pinfunction "NC_38") (pintype "passive+no_connect"))
    )
    (net (code "114") (name "unconnected-(IC7-NC-Pad39)") (class "Default")
      (node (ref "IC7") (pin "39") (pinfunction "NC_39") (pintype "passive+no_connect"))
    )
    (net (code "115") (name "unconnected-(IC7-NC-Pad58)") (class "Default")
      (node (ref "IC7") (pin "58") (pinfunction "NC_58") (pintype "passive+no_connect"))
    )
  )
)
